# AUDIO_ETHNET.net
KiCad netlist of a schematic drawn in Altium Designer
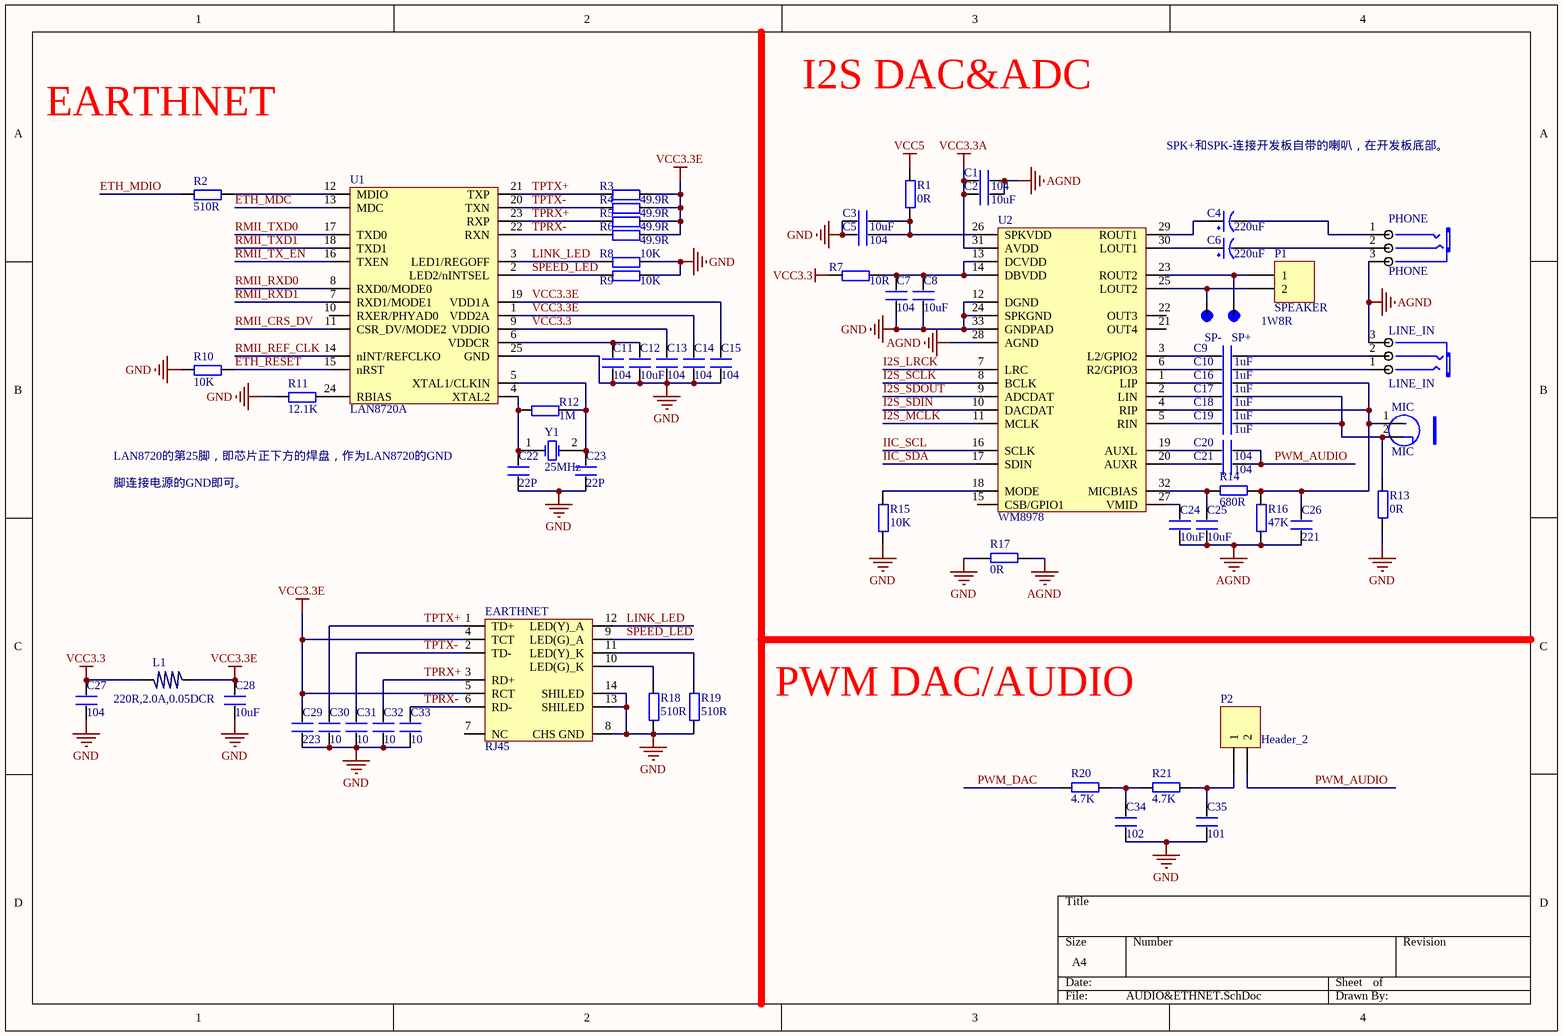
[diagram p0: AUDIO&ETHNET.SchDoc]

(export (version "E")
  (design (tool "Eeschema 10.0.6"))
  (components
    (comp (ref "C1") (value "104") (footprint "R0603") (libsource (lib "Explorer STM32F407封装库") (part "C")))
    (comp (ref "C2")
      (value "10uF")
      (footprint "ZH_library:1206")
      (libsource (lib "Explorer STM32F407封装库") (part "C"))
    )
    (comp (ref "C3")
      (value "10uF")
      (footprint "ZH_library:1206")
      (libsource (lib "Explorer STM32F407封装库") (part "C"))
    )
    (comp (ref "C4")
      (value "220uF")
      (footprint "CC6.56.5")
      (libsource (lib "Explorer STM32F407封装库") (part "CAP"))
    )
    (comp (ref "C5") (value "104") (footprint "R0603") (libsource (lib "Explorer STM32F407封装库") (part "C")))
    (comp (ref "C6")
      (value "220uF")
      (footprint "CC6.56.5")
      (libsource (lib "Explorer STM32F407封装库") (part "CAP"))
    )
    (comp (ref "C7") (value "104") (footprint "R0603") (libsource (lib "Explorer STM32F407封装库") (part "C")))
    (comp (ref "C8")
      (value "10uF")
      (footprint "ZH_library:1206")
      (libsource (lib "Explorer STM32F407封装库") (part "C"))
    )
    (comp (ref "C9") (value "1uF") (footprint "R0603") (libsource (lib "Explorer STM32F407封装库") (part "C")))
    (comp (ref "C10") (value "1uF") (footprint "R0603") (libsource (lib "Explorer STM32F407封装库") (part "C")))
    (comp (ref "C11") (value "104") (footprint "R0603") (libsource (lib "Explorer STM32F407封装库") (part "C")))
    (comp (ref "C12")
      (value "10uF")
      (footprint "ZH_library:1206")
      (libsource (lib "Explorer STM32F407封装库") (part "C"))
    )
    (comp (ref "C13") (value "104") (footprint "R0603") (libsource (lib "Explorer STM32F407封装库") (part "C")))
    (comp (ref "C14") (value "104") (footprint "R0603") (libsource (lib "Explorer STM32F407封装库") (part "C")))
    (comp (ref "C15") (value "104") (footprint "R0603") (libsource (lib "Explorer STM32F407封装库") (part "C")))
    (comp (ref "C16") (value "1uF") (footprint "R0603") (libsource (lib "Explorer STM32F407封装库") (part "C")))
    (comp (ref "C17") (value "1uF") (footprint "R0603") (libsource (lib "Explorer STM32F407封装库") (part "C")))
    (comp (ref "C18") (value "1uF") (footprint "R0603") (libsource (lib "Explorer STM32F407封装库") (part "C")))
    (comp (ref "C19") (value "1uF") (footprint "R0603") (libsource (lib "Explorer STM32F407封装库") (part "C")))
    (comp (ref "C20") (value "104") (footprint "R0603") (libsource (lib "Explorer STM32F407封装库") (part "C")))
    (comp (ref "C21") (value "104") (footprint "R0603") (libsource (lib "Explorer STM32F407封装库") (part "C")))
    (comp (ref "C22") (value "22P") (footprint "R0603") (libsource (lib "Explorer STM32F407封装库") (part "C")))
    (comp (ref "C23") (value "22P") (footprint "R0603") (libsource (lib "Explorer STM32F407封装库") (part "C")))
    (comp (ref "C24")
      (value "10uF")
      (footprint "ZH_library:1206")
      (libsource (lib "Explorer STM32F407封装库") (part "C"))
    )
    (comp (ref "C25")
      (value "10uF")
      (footprint "ZH_library:1206")
      (libsource (lib "Explorer STM32F407封装库") (part "C"))
    )
    (comp (ref "C26") (value "221") (footprint "R0603") (libsource (lib "Explorer STM32F407封装库") (part "C")))
    (comp (ref "C27") (value "104") (footprint "R0603") (libsource (lib "Explorer STM32F407封装库") (part "C")))
    (comp (ref "C28")
      (value "10uF")
      (footprint "ZH_library:1206")
      (libsource (lib "Explorer STM32F407封装库") (part "C"))
    )
    (comp (ref "C29") (value "223") (footprint "R0603") (libsource (lib "Explorer STM32F407封装库") (part "C")))
    (comp (ref "C30") (value "10") (footprint "R0603") (libsource (lib "Explorer STM32F407封装库") (part "C")))
    (comp (ref "C31") (value "10") (footprint "R0603") (libsource (lib "Explorer STM32F407封装库") (part "C")))
    (comp (ref "C32") (value "10") (footprint "R0603") (libsource (lib "Explorer STM32F407封装库") (part "C")))
    (comp (ref "C33") (value "10") (footprint "R0603") (libsource (lib "Explorer STM32F407封装库") (part "C")))
    (comp (ref "C34") (value "102") (footprint "R0603") (libsource (lib "Explorer STM32F407封装库") (part "C")))
    (comp (ref "C35") (value "101") (footprint "R0603") (libsource (lib "Explorer STM32F407封装库") (part "C")))
    (comp (ref "EARTHNET")
      (value "RJ45")
      (footprint "HR911105A")
      (libsource (lib "ENC28J60网络模块封装库") (part "HR911105"))
    )
    (comp (ref "L1")
      (value "220R,2.0A,0.05DCR")
      (footprint "R0603")
      (libsource (lib "Explorer STM32F407封装库") (part "L"))
    )
    (comp (ref "LINE_IN") (value "LINE_IN") (footprint "PHONE_ST") (libsource (lib "") (part "PHONE_M_1")))
    (comp (ref "MIC")
      (value "MIC")
      (footprint "MIC6027")
      (libsource (lib "Explorer STM32F407封装库") (part "MIC"))
    )
    (comp (ref "P1")
      (value "SPEAKER")
      (footprint "HDR1X2")
      (description "Header, 2-Pin")
      (fields (field (name "PUBLISHER") "Altium Limited"))
      (libsource (lib "") (part "Header 2_1"))
    )
    (comp (ref "P2")
      (value "Header_2")
      (footprint "HDR1X2")
      (description "Header, 2-Pin")
      (fields (field (name "PUBLISHER") "Altium Limited"))
      (libsource (lib "Explorer STM32F407封装库") (part "Header 2"))
    )
    (comp (ref "PHONE")
      (value "PHONE")
      (footprint "PHONE_ST")
      (libsource (lib "Explorer STM32F407封装库") (part "PHONE_M"))
    )
    (comp (ref "R1") (value "0R") (footprint "R0603") (libsource (lib "Explorer STM32F407封装库") (part "R")))
    (comp (ref "R2") (value "510R") (footprint "R0603") (libsource (lib "Explorer STM32F407封装库") (part "R")))
    (comp (ref "R3") (value "49.9R") (footprint "R0603") (libsource (lib "Explorer STM32F407封装库") (part "R")))
    (comp (ref "R4") (value "49.9R") (footprint "R0603") (libsource (lib "Explorer STM32F407封装库") (part "R")))
    (comp (ref "R5") (value "49.9R") (footprint "R0603") (libsource (lib "Explorer STM32F407封装库") (part "R")))
    (comp (ref "R6") (value "49.9R") (footprint "R0603") (libsource (lib "Explorer STM32F407封装库") (part "R")))
    (comp (ref "R7") (value "10R") (footprint "R0603") (libsource (lib "Explorer STM32F407封装库") (part "R")))
    (comp (ref "R8") (value "10K") (footprint "R0603") (libsource (lib "Explorer STM32F407封装库") (part "R")))
    (comp (ref "R9") (value "10K") (footprint "R0603") (libsource (lib "Explorer STM32F407封装库") (part "R")))
    (comp (ref "R10") (value "10K") (footprint "R0603") (libsource (lib "Explorer STM32F407封装库") (part "R")))
    (comp (ref "R11")
      (value "12.1K")
      (footprint "R0603")
      (libsource (lib "Explorer STM32F407封装库") (part "R"))
    )
    (comp (ref "R12") (value "1M") (footprint "R0603") (libsource (lib "Explorer STM32F407封装库") (part "R")))
    (comp (ref "R13") (value "0R") (footprint "R0603") (libsource (lib "Explorer STM32F407封装库") (part "R")))
    (comp (ref "R14") (value "680R") (footprint "R0603") (libsource (lib "Explorer STM32F407封装库") (part "R")))
    (comp (ref "R15") (value "10K") (footprint "R0603") (libsource (lib "Explorer STM32F407封装库") (part "R")))
    (comp (ref "R16") (value "47K") (footprint "R0603") (libsource (lib "Explorer STM32F407封装库") (part "R")))
    (comp (ref "R17") (value "0R") (footprint "R0603") (libsource (lib "Explorer STM32F407封装库") (part "R")))
    (comp (ref "R18") (value "510R") (footprint "R0603") (libsource (lib "Explorer STM32F407封装库") (part "R")))
    (comp (ref "R19") (value "510R") (footprint "R0603") (libsource (lib "Explorer STM32F407封装库") (part "R")))
    (comp (ref "R20") (value "4.7K") (footprint "R0603") (libsource (lib "Explorer STM32F407封装库") (part "R")))
    (comp (ref "R21") (value "4.7K") (footprint "R0603") (libsource (lib "Explorer STM32F407封装库") (part "R")))
    (comp (ref "SP+")
      (value "TEST_POINT")
      (footprint "ZH_library:TEST_POINT")
      (libsource (lib "ZH_library") (part "TEST_POINT"))
    )
    (comp (ref "SP-")
      (value "TEST_POINT")
      (footprint "ZH_library:TEST_POINT")
      (libsource (lib "ZH_library") (part "TEST_POINT"))
    )
    (comp (ref "U1")
      (value "LAN8720A")
      (footprint "QFN24_NEW")
      (description "ETH PHY")
      (libsource (lib "Explorer STM32F407封装库") (part "LAN8720"))
    )
    (comp (ref "U2")
      (value "WM8978")
      (footprint "qfn32")
      (description "24bit ADC&DAC")
      (libsource (lib "Explorer STM32F407封装库") (part "WM8978"))
    )
    (comp (ref "Y1")
      (value "25MHz")
      (footprint "XTAL_US")
      (description "Crystal Oscillator")
      (fields (field (name "PUBLISHER") "Altium Limited"))
      (libsource (lib "Explorer STM32F407封装库") (part "XTAL"))
    )
  )
  (nets
    (net (code "1") (name "/ETH_MDC") (class "Default")
      (node (ref "U1") (pin "13") (pinfunction "MDC_13") (pintype "passive"))
    )
    (net (code "2") (name "/ETH_MDIO") (class "Default") (node (ref "R2") (pin "1") (pintype "passive")))
    (net (code "3") (name "/ETH_RESET") (class "Default")
      (node (ref "R10") (pin "2") (pintype "passive"))
      (node (ref "U1") (pin "15") (pinfunction "nRST_15") (pintype "passive"))
    )
    (net (code "4") (name "/I2S_LRCK") (class "Default")
      (node (ref "U2") (pin "7") (pinfunction "LRC_7") (pintype "passive"))
    )
    (net (code "5") (name "/I2S_MCLK") (class "Default")
      (node (ref "U2") (pin "11") (pinfunction "MCLK_11") (pintype "passive"))
    )
    (net (code "6") (name "/I2S_SCLK") (class "Default")
      (node (ref "U2") (pin "8") (pinfunction "BCLK_8") (pintype "passive"))
    )
    (net (code "7") (name "/I2S_SDIN") (class "Default")
      (node (ref "U2") (pin "10") (pinfunction "DACDAT_10") (pintype "passive"))
    )
    (net (code "8") (name "/I2S_SDOUT") (class "Default")
      (node (ref "U2") (pin "9") (pinfunction "ADCDAT_9") (pintype "passive"))
    )
    (net (code "9") (name "/IIC_SCL") (class "Default")
      (node (ref "U2") (pin "16") (pinfunction "SCLK_16") (pintype "passive"))
    )
    (net (code "10") (name "/IIC_SDA") (class "Default")
      (node (ref "U2") (pin "17") (pinfunction "SDIN_17") (pintype "passive"))
    )
    (net (code "11") (name "/LINK_LED") (class "Default")
      (node (ref "EARTHNET") (pin "12") (pinfunction "LED(Y)_A_12") (pintype "passive"))
      (node (ref "R8") (pin "1") (pintype "passive"))
      (node (ref "U1") (pin "3") (pinfunction "LED1/REGOFF_3") (pintype "passive"))
    )
    (net (code "12") (name "/PWM_AUDIO") (class "Default")
      (node (ref "C20") (pin "2") (pintype "passive"))
      (node (ref "C21") (pin "2") (pintype "passive"))
      (node (ref "P2") (pin "2") (pinfunction "2_2") (pintype "passive"))
    )
    (net (code "13") (name "/PWM_DAC") (class "Default") (node (ref "R20") (pin "2") (pintype "passive")))
    (net (code "14") (name "/RMII_CRS_DV") (class "Default")
      (node (ref "U1") (pin "11") (pinfunction "CSR_DV/MODE2_11") (pintype "passive"))
    )
    (net (code "15") (name "/RMII_REF_CLK") (class "Default")
      (node (ref "U1") (pin "14") (pinfunction "nINT/REFCLKO_14") (pintype "passive"))
    )
    (net (code "16") (name "/RMII_RXD0") (class "Default")
      (node (ref "U1") (pin "8") (pinfunction "RXD0/MODE0_8") (pintype "passive"))
    )
    (net (code "17") (name "/RMII_RXD1") (class "Default")
      (node (ref "U1") (pin "7") (pinfunction "RXD1/MODE1_7") (pintype "passive"))
    )
    (net (code "18") (name "/RMII_TXD0") (class "Default")
      (node (ref "U1") (pin "17") (pinfunction "TXD0_17") (pintype "passive"))
    )
    (net (code "19") (name "/RMII_TXD1") (class "Default")
      (node (ref "U1") (pin "18") (pinfunction "TXD1_18") (pintype "passive"))
    )
    (net (code "20") (name "/RMII_TX_EN") (class "Default")
      (node (ref "U1") (pin "16") (pinfunction "TXEN_16") (pintype "passive"))
    )
    (net (code "21") (name "/SPEED_LED") (class "Default")
      (node (ref "EARTHNET") (pin "9") (pinfunction "LED(G)_A_9") (pintype "passive"))
      (node (ref "R9") (pin "1") (pintype "passive"))
      (node (ref "U1") (pin "2") (pinfunction "LED2/nINTSEL_2") (pintype "passive"))
    )
    (net (code "22") (name "/TPRX+") (class "Default")
      (node (ref "C32") (pin "2") (pintype "passive"))
      (node (ref "EARTHNET") (pin "3") (pinfunction "RD+_3") (pintype "passive"))
      (node (ref "R5") (pin "1") (pintype "passive"))
      (node (ref "U1") (pin "23") (pinfunction "RXP_23") (pintype "passive"))
    )
    (net (code "23") (name "/TPRX-") (class "Default")
      (node (ref "C33") (pin "2") (pintype "passive"))
      (node (ref "EARTHNET") (pin "6") (pinfunction "RD-_6") (pintype "passive"))
      (node (ref "R6") (pin "1") (pintype "passive"))
      (node (ref "U1") (pin "22") (pinfunction "RXN_22") (pintype "passive"))
    )
    (net (code "24") (name "/TPTX+") (class "Default")
      (node (ref "C30") (pin "2") (pintype "passive"))
      (node (ref "EARTHNET") (pin "1") (pinfunction "TD+_1") (pintype "passive"))
      (node (ref "R3") (pin "1") (pintype "passive"))
      (node (ref "U1") (pin "21") (pinfunction "TXP_21") (pintype "passive"))
    )
    (net (code "25") (name "/TPTX-") (class "Default")
      (node (ref "C31") (pin "2") (pintype "passive"))
      (node (ref "EARTHNET") (pin "2") (pinfunction "TD-_2") (pintype "passive"))
      (node (ref "R4") (pin "1") (pintype "passive"))
      (node (ref "U1") (pin "20") (pinfunction "TXN_20") (pintype "passive"))
    )
    (net (code "26") (name "AGND") (class "Default")
      (node (ref "C1") (pin "1") (pintype "passive"))
      (node (ref "C2") (pin "1") (pintype "passive"))
      (node (ref "C24") (pin "2") (pintype "passive"))
      (node (ref "C25") (pin "2") (pintype "passive"))
      (node (ref "C26") (pin "2") (pintype "passive"))
      (node (ref "LINE_IN") (pin "3") (pinfunction "COM_3") (pintype "passive"))
      (node (ref "PHONE") (pin "3") (pinfunction "COM_3") (pintype "passive"))
      (node (ref "R16") (pin "1") (pintype "passive"))
      (node (ref "R17") (pin "1") (pintype "passive"))
      (node (ref "U2") (pin "28") (pinfunction "AGND_28") (pintype "passive"))
    )
    (net (code "27") (name "GND") (class "Default")
      (node (ref "C11") (pin "1") (pintype "passive"))
      (node (ref "C12") (pin "1") (pintype "passive"))
      (node (ref "C13") (pin "1") (pintype "passive"))
      (node (ref "C14") (pin "1") (pintype "passive"))
      (node (ref "C15") (pin "1") (pintype "passive"))
      (node (ref "C22") (pin "1") (pintype "passive"))
      (node (ref "C23") (pin "1") (pintype "passive"))
      (node (ref "C27") (pin "1") (pintype "passive"))
      (node (ref "C28") (pin "1") (pintype "passive"))
      (node (ref "C29") (pin "1") (pintype "passive"))
      (node (ref "C3") (pin "2") (pintype "passive"))
      (node (ref "C30") (pin "1") (pintype "passive"))
      (node (ref "C31") (pin "1") (pintype "passive"))
      (node (ref "C32") (pin "1") (pintype "passive"))
      (node (ref "C33") (pin "1") (pintype "passive"))
      (node (ref "C34") (pin "1") (pintype "passive"))
      (node (ref "C35") (pin "1") (pintype "passive"))
      (node (ref "C5") (pin "2") (pintype "passive"))
      (node (ref "C7") (pin "2") (pintype "passive"))
      (node (ref "C8") (pin "2") (pintype "passive"))
      (node (ref "EARTHNET") (pin "13") (pinfunction "SHILED_13") (pintype "passive"))
      (node (ref "EARTHNET") (pin "14") (pinfunction "SHILED_14") (pintype "passive"))
      (node (ref "EARTHNET") (pin "8") (pinfunction "CHS_GND_8") (pintype "passive"))
      (node (ref "R10") (pin "1") (pintype "passive"))
      (node (ref "R11") (pin "1") (pintype "passive"))
      (node (ref "R13") (pin "1") (pintype "passive"))
      (node (ref "R15") (pin "1") (pintype "passive"))
      (node (ref "R17") (pin "2") (pintype "passive"))
      (node (ref "R18") (pin "1") (pintype "passive"))
      (node (ref "R19") (pin "1") (pintype "passive"))
      (node (ref "R8") (pin "2") (pintype "passive"))
      (node (ref "R9") (pin "2") (pintype "passive"))
      (node (ref "U1") (pin "25") (pinfunction "GND_25") (pintype "passive"))
      (node (ref "U2") (pin "12") (pinfunction "DGND_12") (pintype "passive"))
      (node (ref "U2") (pin "24") (pinfunction "SPKGND_24") (pintype "passive"))
      (node (ref "U2") (pin "33") (pinfunction "GNDPAD_33") (pintype "passive"))
    )
    (net (code "28") (name "Net-(C4-GND)") (class "Default")
      (node (ref "C4") (pin "2") (pinfunction "GND_2") (pintype "passive"))
      (node (ref "PHONE") (pin "1") (pinfunction "CHL_1") (pintype "passive"))
    )
    (net (code "29") (name "Net-(C4-VCC)") (class "Default")
      (node (ref "C4") (pin "1") (pinfunction "VCC_1") (pintype "passive"))
      (node (ref "U2") (pin "29") (pinfunction "ROUT1_29") (pintype "passive"))
    )
    (net (code "30") (name "Net-(C6-GND)") (class "Default")
      (node (ref "C6") (pin "2") (pinfunction "GND_2") (pintype "passive"))
      (node (ref "PHONE") (pin "2") (pinfunction "CHR_2") (pintype "passive"))
    )
    (net (code "31") (name "Net-(C6-VCC)") (class "Default")
      (node (ref "C6") (pin "1") (pinfunction "VCC_1") (pintype "passive"))
      (node (ref "U2") (pin "30") (pinfunction "LOUT1_30") (pintype "passive"))
    )
    (net (code "32") (name "Net-(C34-Pad2)") (class "Default")
      (node (ref "C34") (pin "2") (pintype "passive"))
      (node (ref "R20") (pin "1") (pintype "passive"))
      (node (ref "R21") (pin "2") (pintype "passive"))
    )
    (net (code "33") (name "Net-(C35-Pad2)") (class "Default")
      (node (ref "C35") (pin "2") (pintype "passive"))
      (node (ref "P2") (pin "1") (pinfunction "1_1") (pintype "passive"))
      (node (ref "R21") (pin "1") (pintype "passive"))
    )
    (net (code "34") (name "Net-(EARTHNET-LED(G)_K)") (class "Default")
      (node (ref "EARTHNET") (pin "10") (pinfunction "LED(G)_K_10") (pintype "passive"))
      (node (ref "R18") (pin "2") (pintype "passive"))
    )
    (net (code "35") (name "Net-(EARTHNET-LED(Y)_K)") (class "Default")
      (node (ref "EARTHNET") (pin "11") (pinfunction "LED(Y)_K_11") (pintype "passive"))
      (node (ref "R19") (pin "2") (pintype "passive"))
    )
    (net (code "36") (name "Net-(LINE_IN-CHL)") (class "Default")
      (node (ref "C10") (pin "2") (pintype "passive"))
      (node (ref "LINE_IN") (pin "1") (pinfunction "CHL_1") (pintype "passive"))
    )
    (net (code "37") (name "Net-(LINE_IN-CHR)") (class "Default")
      (node (ref "C9") (pin "2") (pintype "passive"))
      (node (ref "LINE_IN") (pin "2") (pinfunction "CHR_2") (pintype "passive"))
    )
    (net (code "38") (name "Net-(MIC-GND)") (class "Default")
      (node (ref "C17") (pin "2") (pintype "passive"))
      (node (ref "C19") (pin "2") (pintype "passive"))
      (node (ref "MIC") (pin "2") (pinfunction "GND_2") (pintype "passive"))
      (node (ref "R13") (pin "2") (pintype "passive"))
    )
    (net (code "39") (name "Net-(MIC-VCC)") (class "Default")
      (node (ref "C16") (pin "2") (pintype "passive"))
      (node (ref "C18") (pin "2") (pintype "passive"))
      (node (ref "C26") (pin "1") (pintype "passive"))
      (node (ref "MIC") (pin "1") (pinfunction "VCC_1") (pintype "passive"))
      (node (ref "R14") (pin "1") (pintype "passive"))
      (node (ref "R16") (pin "2") (pintype "passive"))
    )
    (net (code "40") (name "Net-(U1-MDIO)") (class "Default")
      (node (ref "R2") (pin "2") (pintype "passive"))
      (node (ref "U1") (pin "12") (pinfunction "MDIO_12") (pintype "passive"))
    )
    (net (code "41") (name "Net-(U1-RBIAS)") (class "Default")
      (node (ref "R11") (pin "2") (pintype "passive"))
      (node (ref "U1") (pin "24") (pinfunction "RBIAS_24") (pintype "passive"))
    )
    (net (code "42") (name "Net-(U1-VDDCR)") (class "Default")
      (node (ref "C11") (pin "2") (pintype "passive"))
      (node (ref "C12") (pin "2") (pintype "passive"))
      (node (ref "U1") (pin "6") (pinfunction "VDDCR_6") (pintype "passive"))
    )
    (net (code "43") (name "Net-(U1-XTAL1{slash}CLKIN)") (class "Default")
      (node (ref "C23") (pin "2") (pintype "passive"))
      (node (ref "R12") (pin "2") (pintype "passive"))
      (node (ref "U1") (pin "5") (pinfunction "XTAL1/CLKIN_5") (pintype "passive"))
      (node (ref "Y1") (pin "2") (pinfunction "OSC2_2") (pintype "passive"))
    )
    (net (code "44") (name "Net-(U1-XTAL2)") (class "Default")
      (node (ref "C22") (pin "2") (pintype "passive"))
      (node (ref "R12") (pin "1") (pintype "passive"))
      (node (ref "U1") (pin "4") (pinfunction "XTAL2_4") (pintype "passive"))
      (node (ref "Y1") (pin "1") (pinfunction "OSC1_1") (pintype "passive"))
    )
    (net (code "45") (name "Net-(U2-AUXL)") (class "Default")
      (node (ref "C20") (pin "1") (pintype "passive"))
      (node (ref "U2") (pin "19") (pinfunction "AUXL_19") (pintype "passive"))
    )
    (net (code "46") (name "Net-(U2-AUXR)") (class "Default")
      (node (ref "C21") (pin "1") (pintype "passive"))
      (node (ref "U2") (pin "20") (pinfunction "AUXR_20") (pintype "passive"))
    )
    (net (code "47") (name "Net-(U2-DBVDD)") (class "Default")
      (node (ref "C7") (pin "1") (pintype "passive"))
      (node (ref "C8") (pin "1") (pintype "passive"))
      (node (ref "R7") (pin "2") (pintype "passive"))
      (node (ref "U2") (pin "13") (pinfunction "DCVDD_13") (pintype "passive"))
      (node (ref "U2") (pin "14") (pinfunction "DBVDD_14") (pintype "passive"))
    )
    (net (code "48") (name "Net-(U2-L2{slash}GPIO2)") (class "Default")
      (node (ref "C9") (pin "1") (pintype "passive"))
      (node (ref "U2") (pin "3") (pinfunction "L2/GPIO2_3") (pintype "passive"))
    )
    (net (code "49") (name "Net-(U2-LIN)") (class "Default")
      (node (ref "C17") (pin "1") (pintype "passive"))
      (node (ref "U2") (pin "2") (pinfunction "LIN_2") (pintype "passive"))
    )
    (net (code "50") (name "Net-(U2-LIP)") (class "Default")
      (node (ref "C16") (pin "1") (pintype "passive"))
      (node (ref "U2") (pin "1") (pinfunction "LIP_1") (pintype "passive"))
    )
    (net (code "51") (name "Net-(U2-LOUT2)") (class "Default")
      (node (ref "P1") (pin "2") (pinfunction "2_2") (pintype "passive"))
      (node (ref "SP-") (pin "1") (pinfunction "1_1") (pintype "passive"))
      (node (ref "U2") (pin "25") (pinfunction "LOUT2_25") (pintype "passive"))
    )
    (net (code "52") (name "Net-(U2-MICBIAS)") (class "Default")
      (node (ref "C25") (pin "1") (pintype "passive"))
      (node (ref "R14") (pin "2") (pintype "passive"))
      (node (ref "U2") (pin "32") (pinfunction "MICBIAS_32") (pintype "passive"))
    )
    (net (code "53") (name "Net-(U2-MODE)") (class "Default")
      (node (ref "R15") (pin "2") (pintype "passive"))
      (node (ref "U2") (pin "18") (pinfunction "MODE_18") (pintype "passive"))
    )
    (net (code "54") (name "Net-(U2-R2{slash}GPIO3)") (class "Default")
      (node (ref "C10") (pin "1") (pintype "passive"))
      (node (ref "U2") (pin "6") (pinfunction "R2/GPIO3_6") (pintype "passive"))
    )
    (net (code "55") (name "Net-(U2-RIN)") (class "Default")
      (node (ref "C19") (pin "1") (pintype "passive"))
      (node (ref "U2") (pin "5") (pinfunction "RIN_5") (pintype "passive"))
    )
    (net (code "56") (name "Net-(U2-RIP)") (class "Default")
      (node (ref "C18") (pin "1") (pintype "passive"))
      (node (ref "U2") (pin "4") (pinfunction "RIP_4") (pintype "passive"))
    )
    (net (code "57") (name "Net-(U2-ROUT2)") (class "Default")
      (node (ref "P1") (pin "1") (pinfunction "1_1") (pintype "passive"))
      (node (ref "SP+") (pin "1") (pinfunction "1_1") (pintype "passive"))
      (node (ref "U2") (pin "23") (pinfunction "ROUT2_23") (pintype "passive"))
    )
    (net (code "58") (name "Net-(U2-SPKVDD)") (class "Default")
      (node (ref "C3") (pin "1") (pintype "passive"))
      (node (ref "C5") (pin "1") (pintype "passive"))
      (node (ref "R1") (pin "1") (pintype "passive"))
      (node (ref "U2") (pin "26") (pinfunction "SPKVDD_26") (pintype "passive"))
    )
    (net (code "59") (name "Net-(U2-VMID)") (class "Default")
      (node (ref "C24") (pin "1") (pintype "passive"))
      (node (ref "U2") (pin "27") (pinfunction "VMID_27") (pintype "passive"))
    )
    (net (code "60") (name "VCC3.3") (class "Default")
      (node (ref "C13") (pin "2") (pintype "passive"))
      (node (ref "C27") (pin "2") (pintype "passive"))
      (node (ref "L1") (pin "2") (pintype "passive"))
      (node (ref "R7") (pin "1") (pintype "passive"))
      (node (ref "U1") (pin "9") (pinfunction "VDDIO_9") (pintype "passive"))
    )
    (net (code "61") (name "VCC3.3A") (class "Default")
      (node (ref "C1") (pin "2") (pintype "passive"))
      (node (ref "C2") (pin "2") (pintype "passive"))
      (node (ref "U2") (pin "31") (pinfunction "AVDD_31") (pintype "passive"))
    )
    (net (code "62") (name "VCC3.3E") (class "Default")
      (node (ref "C14") (pin "2") (pintype "passive"))
      (node (ref "C15") (pin "2") (pintype "passive"))
      (node (ref "C28") (pin "2") (pintype "passive"))
      (node (ref "C29") (pin "2") (pintype "passive"))
      (node (ref "EARTHNET") (pin "4") (pinfunction "TCT_4") (pintype "passive"))
      (node (ref "EARTHNET") (pin "5") (pinfunction "RCT_5") (pintype "passive"))
      (node (ref "L1") (pin "1") (pintype "passive"))
      (node (ref "R3") (pin "2") (pintype "passive"))
      (node (ref "R4") (pin "2") (pintype "passive"))
      (node (ref "R5") (pin "2") (pintype "passive"))
      (node (ref "R6") (pin "2") (pintype "passive"))
      (node (ref "U1") (pin "1") (pinfunction "VDD2A_1") (pintype "passive"))
      (node (ref "U1") (pin "19") (pinfunction "VDD1A_19") (pintype "passive"))
    )
    (net (code "63") (name "VCC5") (class "Default") (node (ref "R1") (pin "2") (pintype "passive")))
    (net (code "64") (name "unconnected-(EARTHNET-NC-Pad7)") (class "Default")
      (node (ref "EARTHNET") (pin "7") (pinfunction "NC_7") (pintype "passive"))
    )
    (net (code "65") (name "unconnected-(U1-RXER{slash}PHYAD0-Pad10)") (class "Default")
      (node (ref "U1") (pin "10") (pinfunction "RXER/PHYAD0_10") (pintype "passive"))
    )
    (net (code "66") (name "unconnected-(U2-CSB{slash}GPIO1-Pad15)") (class "Default")
      (node (ref "U2") (pin "15") (pinfunction "CSB/GPIO1_15") (pintype "passive"))
    )
    (net (code "67") (name "unconnected-(U2-OUT3-Pad22)") (class "Default")
      (node (ref "U2") (pin "22") (pinfunction "OUT3_22") (pintype "passive"))
    )
    (net (code "68") (name "unconnected-(U2-OUT4-Pad21)") (class "Default")
      (node (ref "U2") (pin "21") (pinfunction "OUT4_21") (pintype "passive"))
    )
  )
)
